# BatteryManagement.net
KiCad netlist of a schematic drawn in Altium Designer
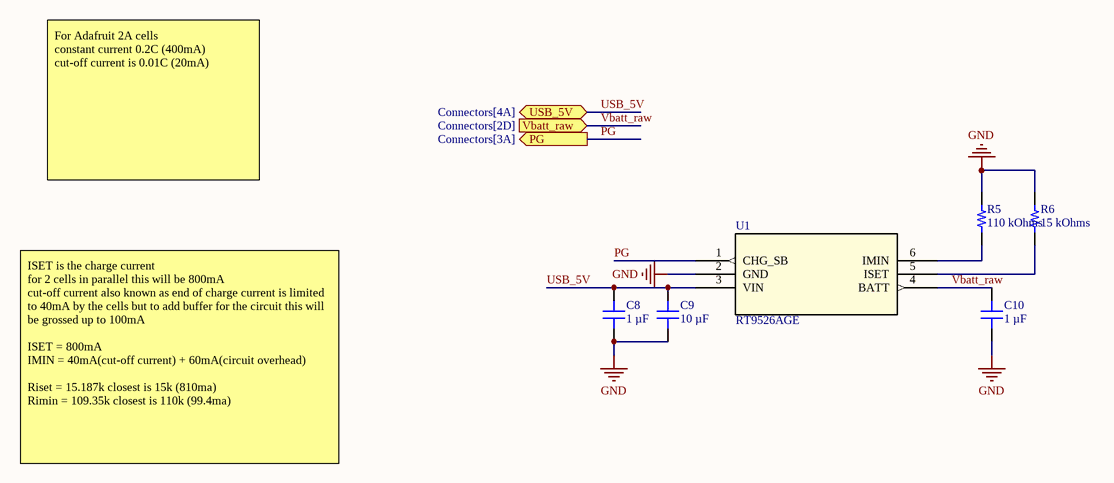
[diagram p0: BatteryManagement.SchDoc]

(export (version "E")
  (design (tool "Eeschema 10.0.6"))
  (components
    (comp (ref "C8")
      (value "1 µF")
      (footprint "CAP 0603_1608")
      (description "CAP CER 1UF 16V X7R 0603")
      (fields
        (field (name "PART NUMBER") "C1608X7R1C105K080AC")
        (field (name "MANUFACTURER") "TDK Corporation")
      )
      (libsource (lib "Celestial Altium Library - altium_library") (part "Capacitor"))
    )
    (comp (ref "C9")
      (value "10 µF")
      (footprint "CAP 0603_1608")
      (description "CAP CER 10UF 25V X5R 0603")
      (fields
        (field (name "PART NUMBER") "GRM188R61E106KA73J")
        (field (name "MANUFACTURER") "Murata Electronics")
      )
      (libsource (lib "Celestial Altium Library - altium_library") (part "Capacitor"))
    )
    (comp (ref "C10")
      (value "1 µF")
      (footprint "CAP 0603_1608")
      (description "CAP CER 1UF 16V X7R 0603")
      (fields
        (field (name "PART NUMBER") "C1608X7R1C105K080AC")
        (field (name "MANUFACTURER") "TDK Corporation")
      )
      (libsource (lib "Celestial Altium Library - altium_library") (part "Capacitor"))
    )
    (comp (ref "R5")
      (value "110 kOhms")
      (footprint "RES 0805_2012")
      (description "RES 110K OHM 1% 1/8W 0805")
      (fields (field (name "PART NUMBER") "RC0805FR-07110KL") (field (name "MANUFACTURER") "Yageo"))
      (libsource (lib "Celestial Altium Library - altium_library") (part "Resistor"))
    )
    (comp (ref "R6")
      (value "15 kOhms")
      (footprint "RES 0805_2012")
      (description "RES 15K OHM 1% 1/8W 0805")
      (fields (field (name "PART NUMBER") "RC0805FR-1315KL") (field (name "MANUFACTURER") "Yageo"))
      (libsource (lib "Celestial Altium Library - altium_library") (part "Resistor"))
    )
    (comp (ref "U1")
      (value "RT9526AGE")
      (footprint "SOT-23-6_RIT")
      (description "No Description Available")
      (fields (field (name "COPYRIGHT") "Copyright (C) 2023 Ultra Librarian. All rights reserved."))
      (libsource (lib "2020-09-26_17-27-19") (part "RT9526AGE"))
    )
  )
  (nets
    (net (code "1") (name "/PG") (class "Default")
      (node (ref "U1") (pin "1") (pinfunction "CHG_SB_1") (pintype "output"))
    )
    (net (code "2") (name "/USB_5V") (class "Default")
      (node (ref "C8") (pin "2") (pinfunction "2_2") (pintype "passive"))
      (node (ref "C9") (pin "2") (pinfunction "2_2") (pintype "passive"))
      (node (ref "U1") (pin "3") (pinfunction "VIN_3") (pintype "power_in"))
    )
    (net (code "3") (name "/Vbatt_raw") (class "Default")
      (node (ref "C10") (pin "2") (pinfunction "2_2") (pintype "passive"))
      (node (ref "U1") (pin "4") (pinfunction "BATT_4") (pintype "output"))
    )
    (net (code "4") (name "GND") (class "Default")
      (node (ref "C10") (pin "1") (pinfunction "1_1") (pintype "passive"))
      (node (ref "C8") (pin "1") (pinfunction "1_1") (pintype "passive"))
      (node (ref "C9") (pin "1") (pinfunction "1_1") (pintype "passive"))
      (node (ref "R5") (pin "2") (pinfunction "2_2") (pintype "passive"))
      (node (ref "R6") (pin "2") (pinfunction "2_2") (pintype "passive"))
      (node (ref "U1") (pin "2") (pinfunction "GND_2") (pintype "passive"))
    )
    (net (code "5") (name "Net-(U1-IMIN)") (class "Default")
      (node (ref "R5") (pin "1") (pinfunction "1_1") (pintype "passive"))
      (node (ref "U1") (pin "6") (pinfunction "IMIN_6") (pintype "passive"))
    )
    (net (code "6") (name "Net-(U1-ISET)") (class "Default")
      (node (ref "R6") (pin "1") (pinfunction "1_1") (pintype "passive"))
      (node (ref "U1") (pin "5") (pinfunction "ISET_5") (pintype "passive"))
    )
  )
)
